# Poi_PCB1_0.net
KiCad netlist of a schematic drawn in EAGLE
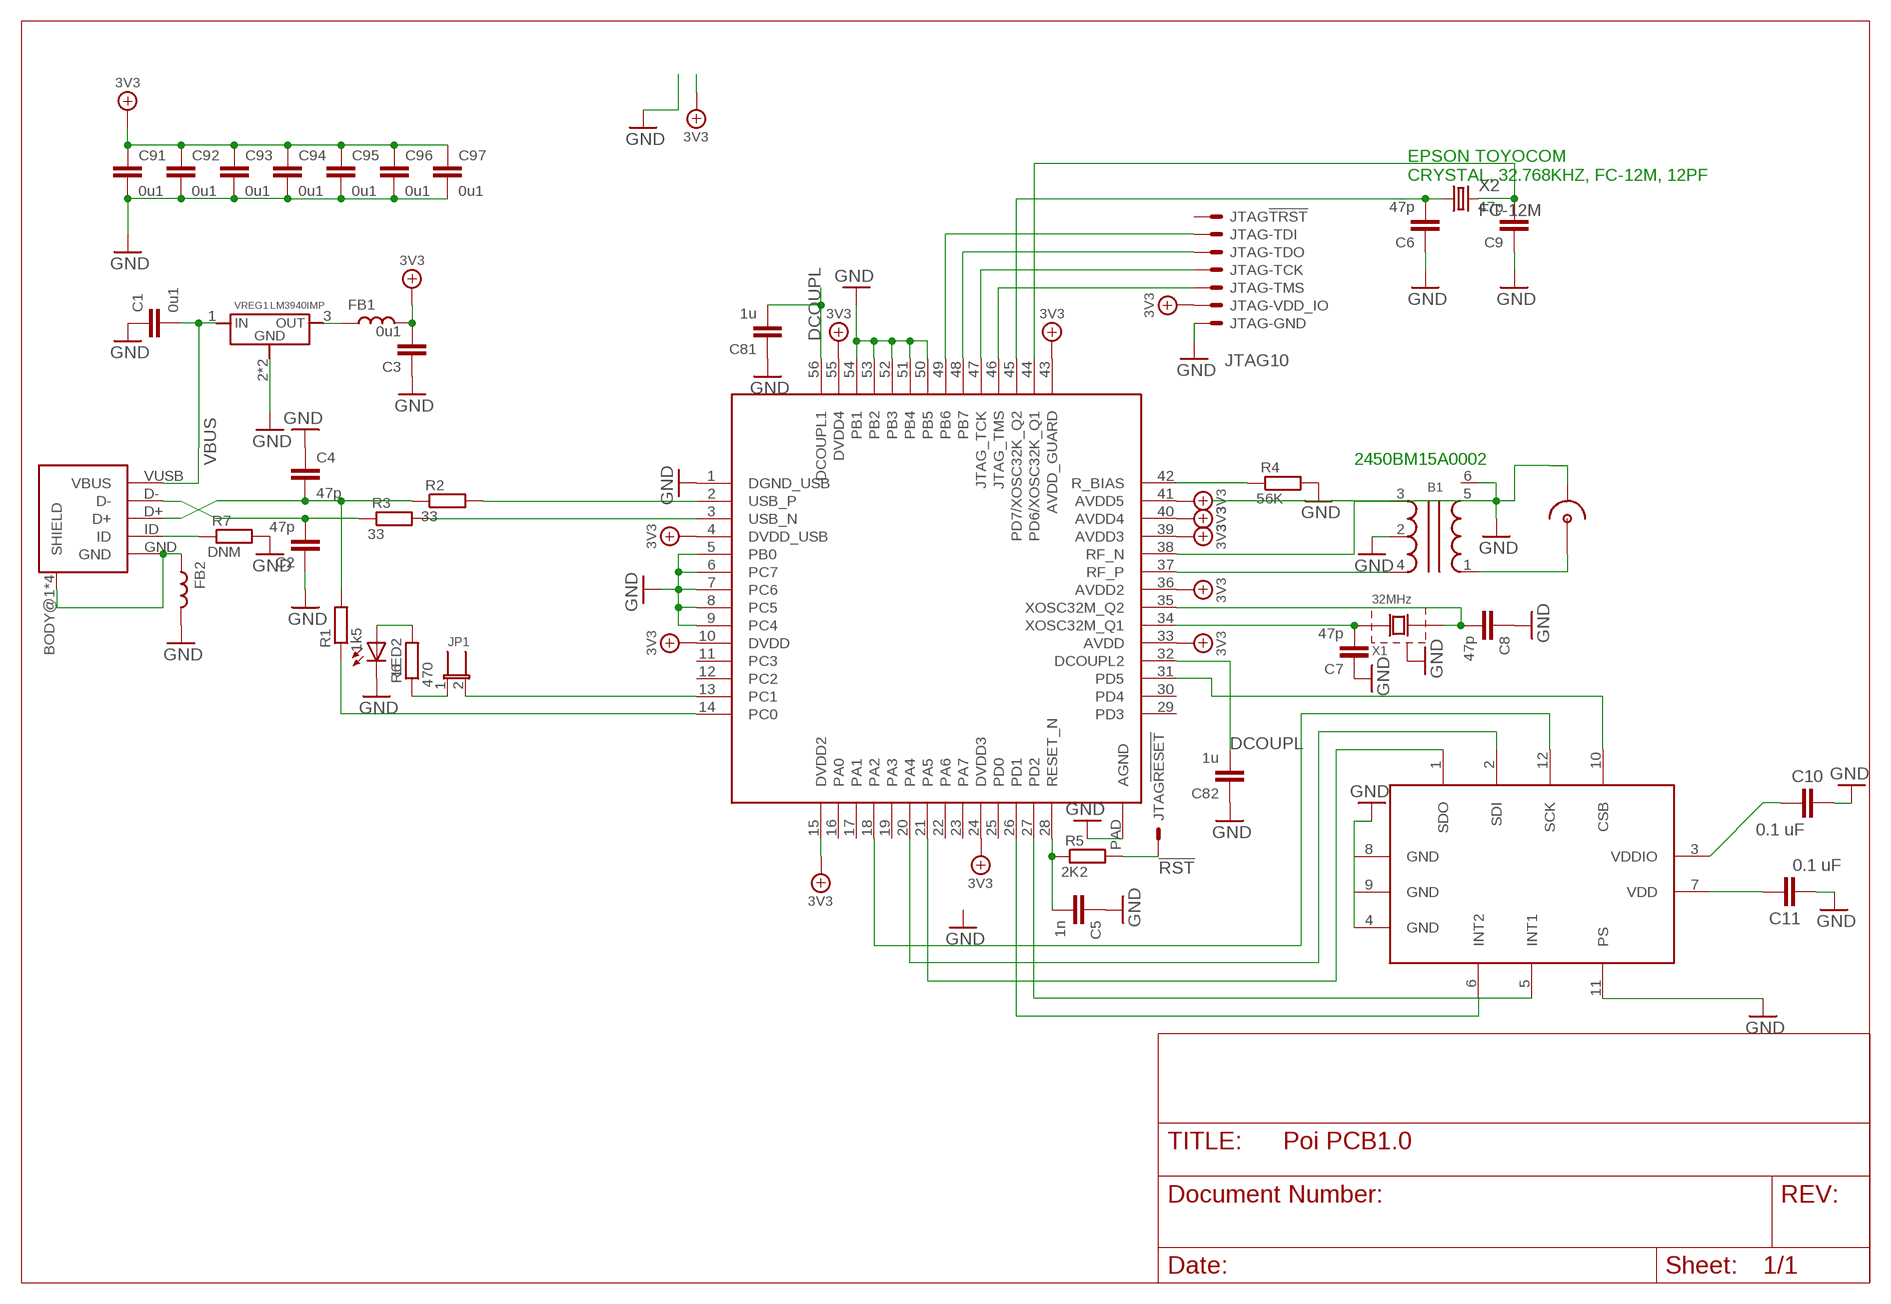
[diagram p0: schematic, sheet 1]

(export (version "E")
  (design (tool "Eeschema 10.0.6"))
  (components
    (comp (ref "B1")
      (value "BALUN")
      (footprint "eagle-import:BALUN-0805")
      (libsource (lib "eagle-import") (part "BALUN"))
    )
    (comp (ref "C1")
      (value "0u1")
      (footprint "eagle-import:C1206")
      (libsource (lib "eagle-import") (part "CC1206"))
    )
    (comp (ref "C2")
      (value "47p")
      (footprint "eagle-import:C0603")
      (libsource (lib "eagle-import") (part "CC0603"))
    )
    (comp (ref "C3")
      (value "0u1")
      (footprint "eagle-import:C1206")
      (libsource (lib "eagle-import") (part "CC1206"))
    )
    (comp (ref "C4")
      (value "47p")
      (footprint "eagle-import:C0603")
      (libsource (lib "eagle-import") (part "CC0603"))
    )
    (comp (ref "C5")
      (value "1n")
      (footprint "eagle-import:C0603")
      (libsource (lib "eagle-import") (part "CC0603"))
    )
    (comp (ref "C6")
      (value "47p")
      (footprint "eagle-import:C0603")
      (libsource (lib "eagle-import") (part "CC0603"))
    )
    (comp (ref "C7")
      (value "47p")
      (footprint "eagle-import:C0603")
      (libsource (lib "eagle-import") (part "CC0603"))
    )
    (comp (ref "C8")
      (value "47p")
      (footprint "eagle-import:C0603")
      (libsource (lib "eagle-import") (part "CC0603"))
    )
    (comp (ref "C9")
      (value "47p")
      (footprint "eagle-import:C0603")
      (libsource (lib "eagle-import") (part "CC0603"))
    )
    (comp (ref "C10")
      (value "0.1 uF")
      (footprint "eagle-import:C0402")
      (libsource (lib "eagle-import") (part "C-EUC0402"))
    )
    (comp (ref "C11")
      (value "0.1 uF")
      (footprint "eagle-import:C0402")
      (libsource (lib "eagle-import") (part "C-EUC0402"))
    )
    (comp (ref "C81")
      (value "1u")
      (footprint "eagle-import:C0402")
      (libsource (lib "eagle-import") (part "CC0402"))
    )
    (comp (ref "C82")
      (value "1u")
      (footprint "eagle-import:C0402")
      (libsource (lib "eagle-import") (part "CC0402"))
    )
    (comp (ref "C91")
      (value "0u1")
      (footprint "eagle-import:C0402")
      (libsource (lib "eagle-import") (part "CC0402"))
    )
    (comp (ref "C92")
      (value "0u1")
      (footprint "eagle-import:C0402")
      (libsource (lib "eagle-import") (part "CC0402"))
    )
    (comp (ref "C93")
      (value "0u1")
      (footprint "eagle-import:C0402")
      (libsource (lib "eagle-import") (part "CC0402"))
    )
    (comp (ref "C94")
      (value "0u1")
      (footprint "eagle-import:C0402")
      (libsource (lib "eagle-import") (part "CC0402"))
    )
    (comp (ref "C95")
      (value "0u1")
      (footprint "eagle-import:C0402")
      (libsource (lib "eagle-import") (part "CC0402"))
    )
    (comp (ref "C96")
      (value "0u1")
      (footprint "eagle-import:C0402")
      (libsource (lib "eagle-import") (part "CC0402"))
    )
    (comp (ref "C97")
      (value "0u1")
      (footprint "eagle-import:C0402")
      (libsource (lib "eagle-import") (part "CC0402"))
    )
    (comp (ref "CN1")
      (value "USB-OTG")
      (footprint "eagle-import:CONN_USB_MINI-B")
      (libsource (lib "eagle-import") (part "USB-OTG"))
    )
    (comp (ref "CN2")
      (value "RF-CONNSMA")
      (footprint "eagle-import:SMA")
      (libsource (lib "eagle-import") (part "RF-CONNSMA"))
    )
    (comp (ref "FB1")
      (value "L0603")
      (footprint "eagle-import:R603")
      (libsource (lib "eagle-import") (part "L0603"))
    )
    (comp (ref "FB2")
      (value "L0603")
      (footprint "eagle-import:R603")
      (libsource (lib "eagle-import") (part "L0603"))
    )
    (comp (ref "JP1")
      (value "JP-2MM-2")
      (footprint "eagle-import:JP-2MM-2")
      (libsource (lib "eagle-import") (part "JP-2MM-2"))
    )
    (comp (ref "JTAG")
      (value "JTAG10")
      (footprint "eagle-import:HDR-2X5-2.00")
      (libsource (lib "eagle-import") (part "JTAG10"))
    )
    (comp (ref "LED2")
      (value "LED805")
      (footprint "eagle-import:LED-805")
      (libsource (lib "eagle-import") (part "LED805"))
    )
    (comp (ref "R1")
      (value "1k5")
      (footprint "eagle-import:R603")
      (libsource (lib "eagle-import") (part "RR603"))
    )
    (comp (ref "R2")
      (value "33")
      (footprint "eagle-import:R603")
      (libsource (lib "eagle-import") (part "RR603"))
    )
    (comp (ref "R3")
      (value "33")
      (footprint "eagle-import:R603")
      (libsource (lib "eagle-import") (part "RR603"))
    )
    (comp (ref "R4")
      (value "56K")
      (footprint "eagle-import:R603")
      (libsource (lib "eagle-import") (part "RR603"))
    )
    (comp (ref "R5")
      (value "2K2")
      (footprint "eagle-import:R603")
      (libsource (lib "eagle-import") (part "RR603"))
    )
    (comp (ref "R6")
      (value "470")
      (footprint "eagle-import:R603")
      (libsource (lib "eagle-import") (part "RR603"))
    )
    (comp (ref "R7")
      (value "DNM")
      (footprint "eagle-import:R603")
      (libsource (lib "eagle-import") (part "RR603"))
    )
    (comp (ref "U$1")
      (value "BMA250")
      (footprint "eagle-import:12LGA_VGG3-D")
      (libsource (lib "eagle-import") (part "BMA250"))
    )
    (comp (ref "U1")
      (value "CC2538")
      (footprint "eagle-import:QFN56")
      (libsource (lib "eagle-import") (part "CC2538"))
    )
    (comp (ref "VREG1")
      (value "LM3940IMP")
      (footprint "eagle-import:SOT223")
      (libsource (lib "eagle-import") (part "LM3940IMP"))
    )
    (comp (ref "X1")
      (value "32MHz")
      (footprint "eagle-import:XTAL-4-3225")
      (libsource (lib "eagle-import") (part "XTAL-43225"))
    )
    (comp (ref "X2")
      (value "FC-12M")
      (footprint "eagle-import:FC-12M")
      (libsource (lib "eagle-import") (part "FC-12M"))
    )
  )
  (nets
    (net (code "1") (name "/DCOUPL") (class "Default")
      (node (ref "C81") (pin "2") (pinfunction "2_2") (pintype "passive"))
      (node (ref "C82") (pin "2") (pinfunction "2_2") (pintype "passive"))
      (node (ref "U1") (pin "32") (pinfunction "DCOUPL2_32") (pintype "bidirectional"))
      (node (ref "U1") (pin "56") (pinfunction "DCOUPL1_56") (pintype "bidirectional"))
    )
    (net (code "2") (name "/VBUS") (class "Default")
      (node (ref "C1") (pin "2") (pinfunction "2_2") (pintype "passive"))
      (node (ref "CN1") (pin "VUSB") (pinfunction "VBUS_VUSB") (pintype "bidirectional"))
      (node (ref "VREG1") (pin "1") (pinfunction "IN_1") (pintype "bidirectional"))
    )
    (net (code "3") (name "/~{RST}") (class "Default")
      (node (ref "JTAG") (pin "4") (pinfunction "S_4") (pintype "passive"))
      (node (ref "R5") (pin "2") (pinfunction "2_2") (pintype "passive"))
    )
    (net (code "4") (name "3V3") (class "Default")
      (node (ref "C3") (pin "2") (pinfunction "2_2") (pintype "passive"))
      (node (ref "C91") (pin "1") (pinfunction "1_1") (pintype "passive"))
      (node (ref "C92") (pin "1") (pinfunction "1_1") (pintype "passive"))
      (node (ref "C93") (pin "1") (pinfunction "1_1") (pintype "passive"))
      (node (ref "C94") (pin "1") (pinfunction "1_1") (pintype "passive"))
      (node (ref "C95") (pin "1") (pinfunction "1_1") (pintype "passive"))
      (node (ref "C96") (pin "1") (pinfunction "1_1") (pintype "passive"))
      (node (ref "C97") (pin "1") (pinfunction "1_1") (pintype "passive"))
      (node (ref "FB1") (pin "2") (pinfunction "P$2_2") (pintype "bidirectional"))
      (node (ref "JTAG") (pin "1") (pinfunction "S_1") (pintype "passive"))
      (node (ref "JTAG") (pin "2") (pinfunction "S_2") (pintype "passive"))
      (node (ref "U1") (pin "10") (pinfunction "DVDD_10") (pintype "bidirectional"))
      (node (ref "U1") (pin "15") (pinfunction "DVDD2_15") (pintype "bidirectional"))
      (node (ref "U1") (pin "24") (pinfunction "DVDD3_24") (pintype "bidirectional"))
      (node (ref "U1") (pin "33") (pinfunction "AVDD_33") (pintype "bidirectional"))
      (node (ref "U1") (pin "36") (pinfunction "AVDD2_36") (pintype "bidirectional"))
      (node (ref "U1") (pin "39") (pinfunction "AVDD3_39") (pintype "bidirectional"))
      (node (ref "U1") (pin "4") (pinfunction "DVDD_USB_4") (pintype "bidirectional"))
      (node (ref "U1") (pin "40") (pinfunction "AVDD4_40") (pintype "bidirectional"))
      (node (ref "U1") (pin "41") (pinfunction "AVDD5_41") (pintype "bidirectional"))
      (node (ref "U1") (pin "43") (pinfunction "AVDD_GUARD_43") (pintype "bidirectional"))
      (node (ref "U1") (pin "55") (pinfunction "DVDD4_55") (pintype "bidirectional"))
    )
    (net (code "5") (name "GND") (class "Default")
      (node (ref "B1") (pin "2") (pinfunction "2_2") (pintype "bidirectional"))
      (node (ref "B1") (pin "5") (pinfunction "5_5") (pintype "bidirectional"))
      (node (ref "B1") (pin "6") (pinfunction "6_6") (pintype "bidirectional"))
      (node (ref "C1") (pin "1") (pinfunction "1_1") (pintype "passive"))
      (node (ref "C10") (pin "1") (pinfunction "1_1") (pintype "passive"))
      (node (ref "C11") (pin "2") (pinfunction "2_2") (pintype "passive"))
      (node (ref "C2") (pin "1") (pinfunction "1_1") (pintype "passive"))
      (node (ref "C3") (pin "1") (pinfunction "1_1") (pintype "passive"))
      (node (ref "C4") (pin "1") (pinfunction "1_1") (pintype "passive"))
      (node (ref "C5") (pin "1") (pinfunction "1_1") (pintype "passive"))
      (node (ref "C6") (pin "1") (pinfunction "1_1") (pintype "passive"))
      (node (ref "C7") (pin "1") (pinfunction "1_1") (pintype "passive"))
      (node (ref "C8") (pin "1") (pinfunction "1_1") (pintype "passive"))
      (node (ref "C81") (pin "1") (pinfunction "1_1") (pintype "passive"))
      (node (ref "C82") (pin "1") (pinfunction "1_1") (pintype "passive"))
      (node (ref "C9") (pin "1") (pinfunction "1_1") (pintype "passive"))
      (node (ref "C91") (pin "2") (pinfunction "2_2") (pintype "passive"))
      (node (ref "C92") (pin "2") (pinfunction "2_2") (pintype "passive"))
      (node (ref "C93") (pin "2") (pinfunction "2_2") (pintype "passive"))
      (node (ref "C94") (pin "2") (pinfunction "2_2") (pintype "passive"))
      (node (ref "C95") (pin "2") (pinfunction "2_2") (pintype "passive"))
      (node (ref "C96") (pin "2") (pinfunction "2_2") (pintype "passive"))
      (node (ref "C97") (pin "2") (pinfunction "2_2") (pintype "passive"))
      (node (ref "CN2") (pin "GND1") (pinfunction "GND_GND1") (pintype "bidirectional"))
      (node (ref "CN2") (pin "GND2") (pinfunction "GND_GND2") (pintype "bidirectional"))
      (node (ref "CN2") (pin "GND3") (pinfunction "GND_GND3") (pintype "bidirectional"))
      (node (ref "CN2") (pin "GND4") (pinfunction "GND_GND4") (pintype "bidirectional"))
      (node (ref "FB2") (pin "2") (pinfunction "P$2_2") (pintype "bidirectional"))
      (node (ref "JTAG") (pin "10") (pinfunction "S_10") (pintype "passive"))
      (node (ref "JTAG") (pin "8") (pinfunction "S_8") (pintype "passive"))
      (node (ref "LED2") (pin "C") (pinfunction "C_C") (pintype "passive"))
      (node (ref "R4") (pin "2") (pinfunction "2_2") (pintype "passive"))
      (node (ref "R7") (pin "2") (pinfunction "2_2") (pintype "passive"))
      (node (ref "U$1") (pin "11") (pinfunction "PS_11") (pintype "bidirectional"))
      (node (ref "U$1") (pin "4") (pinfunction "GND_4") (pintype "bidirectional"))
      (node (ref "U$1") (pin "8") (pinfunction "GND_8") (pintype "bidirectional"))
      (node (ref "U$1") (pin "9") (pinfunction "GND_9") (pintype "bidirectional"))
      (node (ref "U1") (pin "1") (pinfunction "DGND_USB_1") (pintype "bidirectional"))
      (node (ref "U1") (pin "5") (pinfunction "PB0_5") (pintype "bidirectional"))
      (node (ref "U1") (pin "50") (pinfunction "PB5_50") (pintype "bidirectional"))
      (node (ref "U1") (pin "51") (pinfunction "PB4_51") (pintype "bidirectional"))
      (node (ref "U1") (pin "52") (pinfunction "PB3_52") (pintype "bidirectional"))
      (node (ref "U1") (pin "53") (pinfunction "PB2_53") (pintype "bidirectional"))
      (node (ref "U1") (pin "54") (pinfunction "PB1_54") (pintype "bidirectional"))
      (node (ref "U1") (pin "6") (pinfunction "PC7_6") (pintype "bidirectional"))
      (node (ref "U1") (pin "7") (pinfunction "PC6_7") (pintype "bidirectional"))
      (node (ref "U1") (pin "8") (pinfunction "PC5_8") (pintype "bidirectional"))
      (node (ref "U1") (pin "9") (pinfunction "PC4_9") (pintype "bidirectional"))
      (node (ref "U1") (pin "PAD") (pinfunction "AGND_PAD") (pintype "bidirectional"))
      (node (ref "VREG1") (pin "2") (pinfunction "GND_2") (pintype "bidirectional"))
      (node (ref "VREG1") (pin "4") (pinfunction "GND_4") (pintype "bidirectional"))
      (node (ref "X1") (pin "2") (pinfunction "GND1_2") (pintype "bidirectional"))
      (node (ref "X1") (pin "4") (pinfunction "GND1_4") (pintype "bidirectional"))
    )
    (net (code "6") (name "Net-(C2-Pad2)") (class "Default")
      (node (ref "C2") (pin "2") (pinfunction "2_2") (pintype "passive"))
      (node (ref "CN1") (pin "D-") (pinfunction "D-_D-") (pintype "bidirectional"))
      (node (ref "R3") (pin "1") (pinfunction "1_1") (pintype "passive"))
    )
    (net (code "7") (name "Net-(C4-Pad2)") (class "Default")
      (node (ref "C4") (pin "2") (pinfunction "2_2") (pintype "passive"))
      (node (ref "CN1") (pin "D+") (pinfunction "D+_D+") (pintype "bidirectional"))
      (node (ref "R1") (pin "2") (pinfunction "2_2") (pintype "passive"))
      (node (ref "R2") (pin "1") (pinfunction "1_1") (pintype "passive"))
    )
    (net (code "8") (name "Net-(CN1-PadID)") (class "Default")
      (node (ref "CN1") (pin "ID") (pinfunction "ID_ID") (pintype "bidirectional"))
      (node (ref "R7") (pin "1") (pinfunction "1_1") (pintype "passive"))
    )
    (net (code "9") (name "Net-(CN2-SIGNAL)") (class "Default")
      (node (ref "B1") (pin "1") (pinfunction "1_1") (pintype "bidirectional"))
      (node (ref "CN2") (pin "SIG") (pinfunction "SIGNAL_SIG") (pintype "bidirectional"))
    )
    (net (code "10") (name "Net-(FB1-P$1)") (class "Default")
      (node (ref "FB1") (pin "1") (pinfunction "P$1_1") (pintype "bidirectional"))
      (node (ref "VREG1") (pin "3") (pinfunction "OUT_3") (pintype "bidirectional"))
    )
    (net (code "11") (name "Net-(FB2-P$1)") (class "Default")
      (node (ref "CN1") (pin "BODY@1") (pinfunction "SHIELD_BODY@1") (pintype "bidirectional"))
      (node (ref "CN1") (pin "BODY@2") (pinfunction "SHIELD_BODY@2") (pintype "bidirectional"))
      (node (ref "CN1") (pin "BODY@3") (pinfunction "SHIELD_BODY@3") (pintype "bidirectional"))
      (node (ref "CN1") (pin "BODY@4") (pinfunction "SHIELD_BODY@4") (pintype "bidirectional"))
      (node (ref "CN1") (pin "GND") (pinfunction "GND_GND") (pintype "bidirectional"))
      (node (ref "FB2") (pin "1") (pinfunction "P$1_1") (pintype "bidirectional"))
    )
    (net (code "12") (name "Net-(JP1-Pad1)") (class "Default")
      (node (ref "JP1") (pin "1") (pinfunction "1_1") (pintype "bidirectional"))
      (node (ref "R6") (pin "1") (pinfunction "1_1") (pintype "passive"))
    )
    (net (code "13") (name "Net-(JTAGD-S)") (class "Default")
      (node (ref "JTAG") (pin "9") (pinfunction "S_9") (pintype "passive"))
      (node (ref "U1") (pin "47") (pinfunction "JTAG_TCK_47") (pintype "bidirectional"))
    )
    (net (code "14") (name "Net-(JTAGE-S)") (class "Default")
      (node (ref "JTAG") (pin "5") (pinfunction "S_5") (pintype "passive"))
      (node (ref "U1") (pin "49") (pinfunction "PB6_49") (pintype "bidirectional"))
    )
    (net (code "15") (name "Net-(JTAGF-S)") (class "Default")
      (node (ref "JTAG") (pin "6") (pinfunction "S_6") (pintype "passive"))
      (node (ref "U1") (pin "48") (pinfunction "PB7_48") (pintype "bidirectional"))
    )
    (net (code "16") (name "Net-(JTAGG-S)") (class "Default")
      (node (ref "JTAG") (pin "7") (pinfunction "S_7") (pintype "passive"))
      (node (ref "U1") (pin "46") (pinfunction "JTAG_TMS_46") (pintype "bidirectional"))
    )
    (net (code "17") (name "Net-(LED2-PadA)") (class "Default")
      (node (ref "LED2") (pin "A") (pinfunction "A_A") (pintype "passive"))
      (node (ref "R6") (pin "2") (pinfunction "2_2") (pintype "passive"))
    )
    (net (code "18") (name "Net-(U$1-CSB)") (class "Default")
      (node (ref "U$1") (pin "10") (pinfunction "CSB_10") (pintype "bidirectional"))
      (node (ref "U1") (pin "31") (pinfunction "PD5_31") (pintype "bidirectional"))
    )
    (net (code "19") (name "Net-(U$1-INT1)") (class "Default")
      (node (ref "U$1") (pin "5") (pinfunction "INT1_5") (pintype "bidirectional"))
      (node (ref "U1") (pin "27") (pinfunction "PD2_27") (pintype "bidirectional"))
    )
    (net (code "20") (name "Net-(U$1-INT2)") (class "Default")
      (node (ref "U$1") (pin "6") (pinfunction "INT2_6") (pintype "bidirectional"))
      (node (ref "U1") (pin "26") (pinfunction "PD1_26") (pintype "bidirectional"))
    )
    (net (code "21") (name "Net-(U$1-SCK)") (class "Default")
      (node (ref "U$1") (pin "12") (pinfunction "SCK_12") (pintype "bidirectional"))
      (node (ref "U1") (pin "18") (pinfunction "PA2_18") (pintype "bidirectional"))
    )
    (net (code "22") (name "Net-(U$1-SDI)") (class "Default")
      (node (ref "U$1") (pin "2") (pinfunction "SDI_2") (pintype "bidirectional"))
      (node (ref "U1") (pin "20") (pinfunction "PA4_20") (pintype "bidirectional"))
    )
    (net (code "23") (name "Net-(U$1-SDO)") (class "Default")
      (node (ref "U$1") (pin "1") (pinfunction "SDO_1") (pintype "bidirectional"))
      (node (ref "U1") (pin "21") (pinfunction "PA5_21") (pintype "bidirectional"))
    )
    (net (code "24") (name "Net-(U$1-VDD)") (class "Default")
      (node (ref "C11") (pin "1") (pinfunction "1_1") (pintype "passive"))
      (node (ref "U$1") (pin "7") (pinfunction "VDD_7") (pintype "bidirectional"))
    )
    (net (code "25") (name "Net-(U$1-VDDIO)") (class "Default")
      (node (ref "C10") (pin "2") (pinfunction "2_2") (pintype "passive"))
      (node (ref "U$1") (pin "3") (pinfunction "VDDIO_3") (pintype "bidirectional"))
    )
    (net (code "26") (name "Net-(U1-PC0)") (class "Default")
      (node (ref "R1") (pin "1") (pinfunction "1_1") (pintype "passive"))
      (node (ref "U1") (pin "14") (pinfunction "PC0_14") (pintype "bidirectional"))
    )
    (net (code "27") (name "Net-(U1-PC1)") (class "Default")
      (node (ref "JP1") (pin "2") (pinfunction "2_2") (pintype "bidirectional"))
      (node (ref "U1") (pin "13") (pinfunction "PC1_13") (pintype "bidirectional"))
    )
    (net (code "28") (name "Net-(U1-PD6{slash}XOSC32K_Q1)") (class "Default")
      (node (ref "C9") (pin "2") (pinfunction "2_2") (pintype "passive"))
      (node (ref "U1") (pin "44") (pinfunction "PD6/XOSC32K_Q1_44") (pintype "bidirectional"))
      (node (ref "X2") (pin "2") (pinfunction "2_2") (pintype "passive"))
    )
    (net (code "29") (name "Net-(U1-PD7{slash}XOSC32K_Q2)") (class "Default")
      (node (ref "C6") (pin "2") (pinfunction "2_2") (pintype "passive"))
      (node (ref "U1") (pin "45") (pinfunction "PD7/XOSC32K_Q2_45") (pintype "bidirectional"))
      (node (ref "X2") (pin "1") (pinfunction "1_1") (pintype "passive"))
    )
    (net (code "30") (name "Net-(U1-RESET_N)") (class "Default")
      (node (ref "C5") (pin "2") (pinfunction "2_2") (pintype "passive"))
      (node (ref "R5") (pin "1") (pinfunction "1_1") (pintype "passive"))
      (node (ref "U1") (pin "28") (pinfunction "RESET_N_28") (pintype "bidirectional"))
    )
    (net (code "31") (name "Net-(U1-RF_N)") (class "Default")
      (node (ref "B1") (pin "3") (pinfunction "3_3") (pintype "bidirectional"))
      (node (ref "U1") (pin "38") (pinfunction "RF_N_38") (pintype "bidirectional"))
    )
    (net (code "32") (name "Net-(U1-RF_P)") (class "Default")
      (node (ref "B1") (pin "4") (pinfunction "4_4") (pintype "bidirectional"))
      (node (ref "U1") (pin "37") (pinfunction "RF_P_37") (pintype "bidirectional"))
    )
    (net (code "33") (name "Net-(U1-R_BIAS)") (class "Default")
      (node (ref "R4") (pin "1") (pinfunction "1_1") (pintype "passive"))
      (node (ref "U1") (pin "42") (pinfunction "R_BIAS_42") (pintype "bidirectional"))
    )
    (net (code "34") (name "Net-(U1-USB_N)") (class "Default")
      (node (ref "R3") (pin "2") (pinfunction "2_2") (pintype "passive"))
      (node (ref "U1") (pin "3") (pinfunction "USB_N_3") (pintype "bidirectional"))
    )
    (net (code "35") (name "Net-(U1-USB_P)") (class "Default")
      (node (ref "R2") (pin "2") (pinfunction "2_2") (pintype "passive"))
      (node (ref "U1") (pin "2") (pinfunction "USB_P_2") (pintype "bidirectional"))
    )
    (net (code "36") (name "Net-(U1-XOSC32M_Q1)") (class "Default")
      (node (ref "C7") (pin "2") (pinfunction "2_2") (pintype "passive"))
      (node (ref "U1") (pin "34") (pinfunction "XOSC32M_Q1_34") (pintype "bidirectional"))
      (node (ref "X1") (pin "1") (pinfunction "X1_1") (pintype "bidirectional"))
    )
    (net (code "37") (name "Net-(U1-XOSC32M_Q2)") (class "Default")
      (node (ref "C8") (pin "2") (pinfunction "2_2") (pintype "passive"))
      (node (ref "U1") (pin "35") (pinfunction "XOSC32M_Q2_35") (pintype "bidirectional"))
      (node (ref "X1") (pin "3") (pinfunction "X2_3") (pintype "bidirectional"))
    )
    (net (code "38") (name "unconnected-(JTAGB-S-Pad3)") (class "Default")
      (node (ref "JTAG") (pin "3") (pinfunction "S_3") (pintype "passive"))
    )
    (net (code "39") (name "unconnected-(U1-PA0-Pad16)") (class "Default")
      (node (ref "U1") (pin "16") (pinfunction "PA0_16") (pintype "bidirectional"))
    )
    (net (code "40") (name "unconnected-(U1-PA1-Pad17)") (class "Default")
      (node (ref "U1") (pin "17") (pinfunction "PA1_17") (pintype "bidirectional"))
    )
    (net (code "41") (name "unconnected-(U1-PA3-Pad19)") (class "Default")
      (node (ref "U1") (pin "19") (pinfunction "PA3_19") (pintype "bidirectional"))
    )
    (net (code "42") (name "unconnected-(U1-PA6-Pad22)") (class "Default")
      (node (ref "U1") (pin "22") (pinfunction "PA6_22") (pintype "bidirectional"))
    )
    (net (code "43") (name "unconnected-(U1-PA7-Pad23)") (class "Default")
      (node (ref "U1") (pin "23") (pinfunction "PA7_23") (pintype "bidirectional"))
    )
    (net (code "44") (name "unconnected-(U1-PC2-Pad12)") (class "Default")
      (node (ref "U1") (pin "12") (pinfunction "PC2_12") (pintype "bidirectional"))
    )
    (net (code "45") (name "unconnected-(U1-PC3-Pad11)") (class "Default")
      (node (ref "U1") (pin "11") (pinfunction "PC3_11") (pintype "bidirectional"))
    )
    (net (code "46") (name "unconnected-(U1-PD0-Pad25)") (class "Default")
      (node (ref "U1") (pin "25") (pinfunction "PD0_25") (pintype "bidirectional"))
    )
    (net (code "47") (name "unconnected-(U1-PD3-Pad29)") (class "Default")
      (node (ref "U1") (pin "29") (pinfunction "PD3_29") (pintype "bidirectional"))
    )
    (net (code "48") (name "unconnected-(U1-PD4-Pad30)") (class "Default")
      (node (ref "U1") (pin "30") (pinfunction "PD4_30") (pintype "bidirectional"))
    )
  )
)
